# teensy_cfd.net
KiCad netlist of a schematic drawn in EAGLE
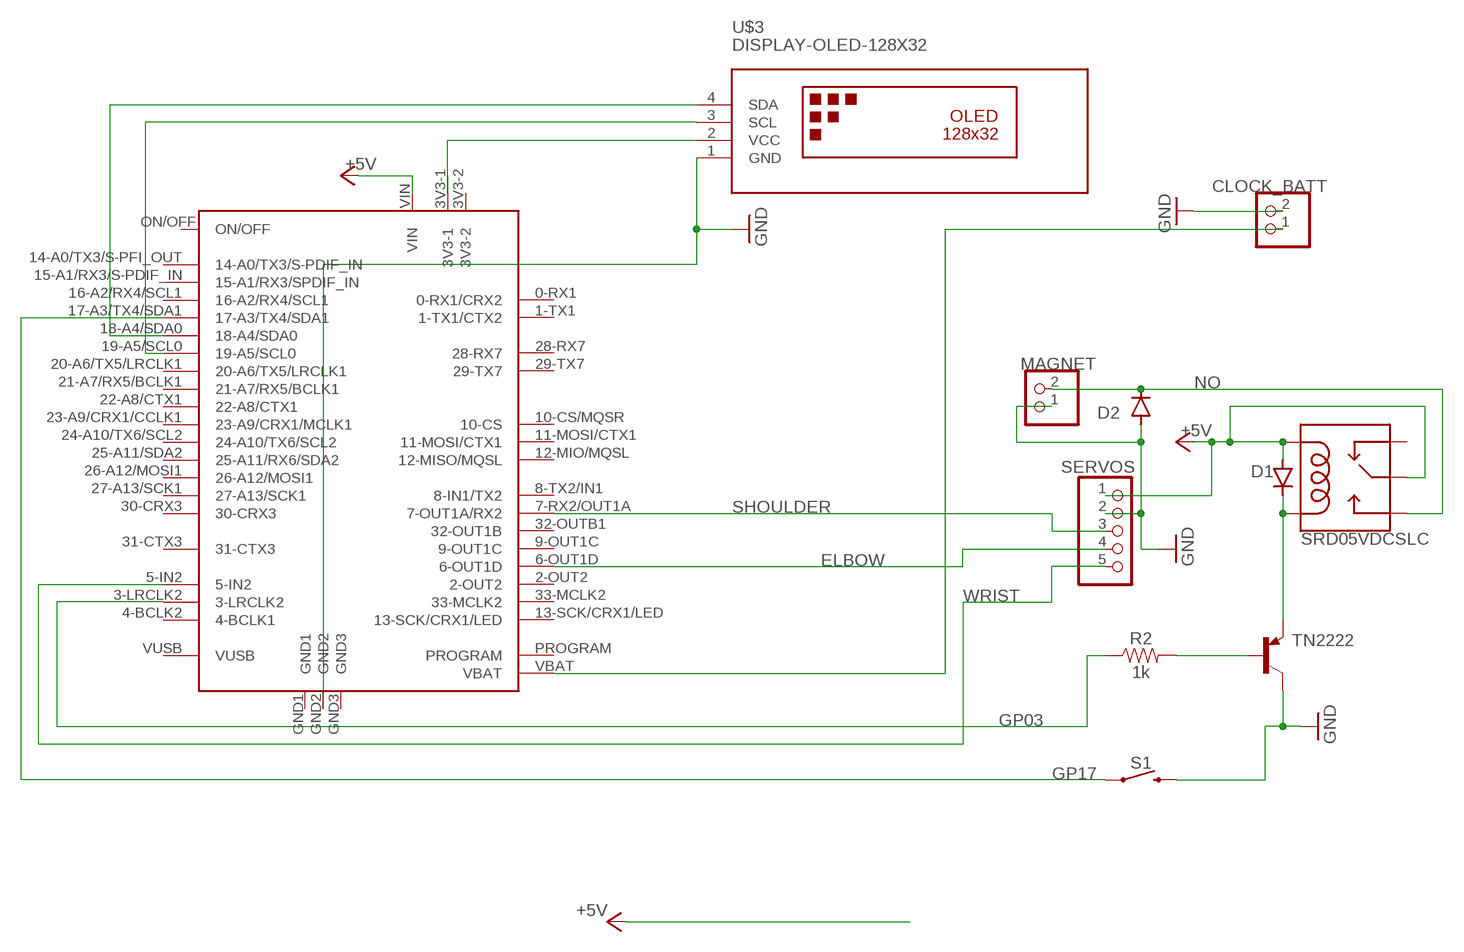
[diagram p0: schematic, sheet 1]

(export (version "E")
  (design (tool "Eeschema 10.0.6"))
  (components
    (comp (ref "CLOCK_BATT")
      (value "PINHD-1X2")
      (footprint "eagle-import:1X02")
      (libsource (lib "eagle-import") (part "PINHD-1X2"))
    )
    (comp (ref "D1")
      (value "1N4004")
      (footprint "eagle-import:DO41-10")
      (libsource (lib "eagle-import") (part "1N4004"))
    )
    (comp (ref "D2")
      (value "1N4004")
      (footprint "eagle-import:DO41-10")
      (libsource (lib "eagle-import") (part "1N4004"))
    )
    (comp (ref "MAGNET")
      (value "PINHD-1X2")
      (footprint "eagle-import:1X02")
      (libsource (lib "eagle-import") (part "PINHD-1X2"))
    )
    (comp (ref "R2")
      (value "1k")
      (footprint "eagle-import:AXIAL-0.3")
      (libsource (lib "eagle-import") (part "1KOHM-HORIZ-1/4W-1%"))
    )
    (comp (ref "S1")
      (value "MOMENTARY-SWITCH-SPST-PTH-6.0MM")
      (footprint "eagle-import:TACTILE_SWITCH_PTH_6.0MM")
      (libsource (lib "eagle-import") (part "MOMENTARY-SWITCH-SPST-PTH-6.0MM"))
    )
    (comp (ref "SERVOS")
      (value "PINHD-1X5")
      (footprint "eagle-import:1X05")
      (libsource (lib "eagle-import") (part "PINHD-1X5"))
    )
    (comp (ref "SRD05VDCSLC")
      (value "RELAYPTH")
      (footprint "eagle-import:SRD-05VDC-SL-C")
      (libsource (lib "eagle-import") (part "RELAYPTH"))
    )
    (comp (ref "TN2222")
      (value "TN2222")
      (footprint "eagle-import:TO92")
      (libsource (lib "eagle-import") (part "PNPTO92_"))
    )
    (comp (ref "U$1")
      (value "TEENSY40")
      (footprint "eagle-import:TEENSY40")
      (libsource (lib "eagle-import") (part "TEENSY40"))
    )
    (comp (ref "U$3")
      (value "DISPLAY-OLED-128X32")
      (footprint "eagle-import:DISPLAY-OLED-128X32")
      (libsource (lib "eagle-import") (part "DISPLAY-OLED-128X32"))
    )
  )
  (nets
    (net (code "1") (name "+5V") (class "Default")
      (node (ref "D1") (pin "A") (pinfunction "A_A") (pintype "passive"))
      (node (ref "SERVOS") (pin "1") (pinfunction "1_1") (pintype "passive"))
      (node (ref "SRD05VDCSLC") (pin "COIL1") (pinfunction "COIL1_COIL1") (pintype "bidirectional"))
      (node (ref "SRD05VDCSLC") (pin "SWCOMMON") (pinfunction "SWCOMMON_SWCOMMON") (pintype "bidirectional"))
      (node (ref "U$1") (pin "VIN") (pinfunction "VIN_VIN") (pintype "bidirectional"))
    )
    (net (code "2") (name "/ELBOW") (class "Default")
      (node (ref "SERVOS") (pin "4") (pinfunction "4_4") (pintype "passive"))
      (node (ref "U$1") (pin "6-OUT1D") (pinfunction "6-OUT1D_6-OUT1D") (pintype "bidirectional"))
    )
    (net (code "3") (name "/GP03") (class "Default")
      (node (ref "R2") (pin "P$1") (pinfunction "1_P$1") (pintype "passive"))
      (node (ref "U$1") (pin "3-LRCLK2") (pinfunction "3-LRCLK2_3-LRCLK2") (pintype "bidirectional"))
    )
    (net (code "4") (name "/GP17") (class "Default")
      (node (ref "S1") (pin "1") (pinfunction "1_1") (pintype "passive"))
      (node (ref "U$1") (pin "17-A3/TX4/SDA1") (pinfunction "17-A3/TX4/SDA1_17-A3/TX4/SDA1") (pintype "bidirectional"))
    )
    (net (code "5") (name "/NO") (class "Default")
      (node (ref "D2") (pin "C") (pinfunction "C_C") (pintype "passive"))
      (node (ref "MAGNET") (pin "2") (pinfunction "2_2") (pintype "passive"))
      (node (ref "SRD05VDCSLC") (pin "SWOPEN") (pinfunction "SWOPEN_SWOPEN") (pintype "bidirectional"))
    )
    (net (code "6") (name "/SHOULDER") (class "Default")
      (node (ref "SERVOS") (pin "3") (pinfunction "3_3") (pintype "passive"))
      (node (ref "U$1") (pin "7-RX2/OUT1A") (pinfunction "7-OUT1A/RX2_7-RX2/OUT1A") (pintype "bidirectional"))
    )
    (net (code "7") (name "/WRIST") (class "Default")
      (node (ref "SERVOS") (pin "5") (pinfunction "5_5") (pintype "passive"))
      (node (ref "U$1") (pin "5-IN2") (pinfunction "5-IN2_5-IN2") (pintype "bidirectional"))
    )
    (net (code "8") (name "GND") (class "Default")
      (node (ref "CLOCK_BATT") (pin "2") (pinfunction "2_2") (pintype "passive"))
      (node (ref "D2") (pin "A") (pinfunction "A_A") (pintype "passive"))
      (node (ref "MAGNET") (pin "1") (pinfunction "1_1") (pintype "passive"))
      (node (ref "S1") (pin "3") (pinfunction "2_3") (pintype "passive"))
      (node (ref "SERVOS") (pin "2") (pinfunction "2_2") (pintype "passive"))
      (node (ref "TN2222") (pin "1") (pinfunction "C_1") (pintype "passive"))
      (node (ref "U$1") (pin "GND2") (pinfunction "GND2_GND2") (pintype "bidirectional"))
      (node (ref "U$3") (pin "1") (pinfunction "GND_1") (pintype "power_in"))
    )
    (net (code "9") (name "Net-(CLOCK_BATT-Pad1)") (class "Default")
      (node (ref "CLOCK_BATT") (pin "1") (pinfunction "1_1") (pintype "passive"))
      (node (ref "U$1") (pin "VBAT") (pinfunction "VBAT_VBAT") (pintype "bidirectional"))
    )
    (net (code "10") (name "Net-(R2-2)") (class "Default")
      (node (ref "R2") (pin "P$2") (pinfunction "2_P$2") (pintype "passive"))
      (node (ref "TN2222") (pin "2") (pinfunction "B_2") (pintype "passive"))
    )
    (net (code "11") (name "Net-(TN2222-E)") (class "Default")
      (node (ref "D1") (pin "C") (pinfunction "C_C") (pintype "passive"))
      (node (ref "SRD05VDCSLC") (pin "COIL0") (pinfunction "COIL0_COIL0") (pintype "bidirectional"))
      (node (ref "TN2222") (pin "3") (pinfunction "E_3") (pintype "passive"))
    )
    (net (code "12") (name "Net-(U$3-SCL)") (class "Default")
      (node (ref "U$1") (pin "19-A5/SCL0") (pinfunction "19-A5/SCL0_19-A5/SCL0") (pintype "bidirectional"))
      (node (ref "U$3") (pin "3") (pinfunction "SCL_3") (pintype "bidirectional"))
    )
    (net (code "13") (name "Net-(U$3-SDA)") (class "Default")
      (node (ref "U$1") (pin "18-A4/SDA0") (pinfunction "18-A4/SDA0_18-A4/SDA0") (pintype "bidirectional"))
      (node (ref "U$3") (pin "4") (pinfunction "SDA_4") (pintype "bidirectional"))
    )
    (net (code "14") (name "Net-(U$3-VCC)") (class "Default")
      (node (ref "U$1") (pin "3V3-1") (pinfunction "3V3-1_3V3-1") (pintype "bidirectional"))
      (node (ref "U$3") (pin "2") (pinfunction "VCC_2") (pintype "power_in"))
    )
    (net (code "15") (name "unconnected-(SRD05VDCSLC-SWCLOSE-PadSWCLOSED)") (class "Default")
      (node (ref "SRD05VDCSLC") (pin "SWCLOSED") (pinfunction "SWCLOSE_SWCLOSED") (pintype "bidirectional"))
    )
    (net (code "16") (name "unconnected-(U$1-0-RX1{slash}CRX2-Pad0-RX1)") (class "Default")
      (node (ref "U$1") (pin "0-RX1") (pinfunction "0-RX1/CRX2_0-RX1") (pintype "bidirectional"))
    )
    (net (code "17") (name "unconnected-(U$1-1-TX1{slash}CTX2-Pad1-TX1)") (class "Default")
      (node (ref "U$1") (pin "1-TX1") (pinfunction "1-TX1/CTX2_1-TX1") (pintype "bidirectional"))
    )
    (net (code "18") (name "unconnected-(U$1-4-BCLK1-Pad4-BCLK2)") (class "Default")
      (node (ref "U$1") (pin "4-BCLK2") (pinfunction "4-BCLK1_4-BCLK2") (pintype "bidirectional"))
    )
    (net (code "19") (name "unconnected-(U$1-8-IN1{slash}TX2-Pad8-TX2{slash}IN1)") (class "Default")
      (node (ref "U$1") (pin "8-TX2/IN1") (pinfunction "8-IN1/TX2_8-TX2/IN1") (pintype "bidirectional"))
    )
    (net (code "20") (name "unconnected-(U$1-10-CS-Pad10-CS{slash}MQSR)") (class "Default")
      (node (ref "U$1") (pin "10-CS/MQSR") (pinfunction "10-CS_10-CS/MQSR") (pintype "bidirectional"))
    )
    (net (code "21") (name "unconnected-(U$1-12-MISO{slash}MQSL-Pad12-MIO{slash}MQSL)") (class "Default")
      (node (ref "U$1") (pin "12-MIO/MQSL") (pinfunction "12-MISO/MQSL_12-MIO/MQSL") (pintype "bidirectional"))
    )
    (net (code "22") (name "unconnected-(U$1-14-A0{slash}TX3{slash}S-PDIF_IN-Pad14-A0{slash}TX3{slash}S-PFI_OUT)") (class "Default")
      (node (ref "U$1") (pin "14-A0/TX3/S-PFI_OUT") (pinfunction "14-A0/TX3/S-PDIF_IN_14-A0/TX3/S-PFI_OUT") (pintype "bidirectional"))
    )
    (net (code "23") (name "unconnected-(U$1-15-A1{slash}RX3{slash}SPDIF_IN-Pad15-A1{slash}RX3{slash}S-PDIF_IN)") (class "Default")
      (node (ref "U$1") (pin "15-A1/RX3/S-PDIF_IN") (pinfunction "15-A1/RX3/SPDIF_IN_15-A1/RX3/S-PDIF_IN") (pintype "bidirectional"))
    )
    (net (code "24") (name "unconnected-(U$1-23-A9{slash}CRX1{slash}MCLK1-Pad23-A9{slash}CRX1{slash}CCLK1)") (class "Default")
      (node (ref "U$1") (pin "23-A9/CRX1/CCLK1") (pinfunction "23-A9/CRX1/MCLK1_23-A9/CRX1/CCLK1") (pintype "bidirectional"))
    )
    (net (code "25") (name "unconnected-(U$1-25-A11{slash}RX6{slash}SDA2-Pad25-A11{slash}SDA2)") (class "Default")
      (node (ref "U$1") (pin "25-A11/SDA2") (pinfunction "25-A11/RX6/SDA2_25-A11/SDA2") (pintype "bidirectional"))
    )
    (net (code "26") (name "unconnected-(U$1-32-OUT1B-Pad32-OUTB1)") (class "Default")
      (node (ref "U$1") (pin "32-OUTB1") (pinfunction "32-OUT1B_32-OUTB1") (pintype "bidirectional"))
    )
    (net (code "27") (name "unconnected-(U$1-Pad2-OUT2)") (class "Default")
      (node (ref "U$1") (pin "2-OUT2") (pinfunction "2-OUT2_2-OUT2") (pintype "bidirectional"))
    )
    (net (code "28") (name "unconnected-(U$1-Pad3V3-2)") (class "Default")
      (node (ref "U$1") (pin "3V3-2") (pinfunction "3V3-2_3V3-2") (pintype "bidirectional"))
    )
    (net (code "29") (name "unconnected-(U$1-Pad9-OUT1C)") (class "Default")
      (node (ref "U$1") (pin "9-OUT1C") (pinfunction "9-OUT1C_9-OUT1C") (pintype "bidirectional"))
    )
    (net (code "30") (name "unconnected-(U$1-Pad11-MOSI{slash}CTX1)") (class "Default")
      (node (ref "U$1") (pin "11-MOSI/CTX1") (pinfunction "11-MOSI/CTX1_11-MOSI/CTX1") (pintype "bidirectional"))
    )
    (net (code "31") (name "unconnected-(U$1-Pad13-SCK{slash}CRX1{slash}LED)") (class "Default")
      (node (ref "U$1") (pin "13-SCK/CRX1/LED") (pinfunction "13-SCK/CRX1/LED_13-SCK/CRX1/LED") (pintype "bidirectional"))
    )
    (net (code "32") (name "unconnected-(U$1-Pad16-A2{slash}RX4{slash}SCL1)") (class "Default")
      (node (ref "U$1") (pin "16-A2/RX4/SCL1") (pinfunction "16-A2/RX4/SCL1_16-A2/RX4/SCL1") (pintype "bidirectional"))
    )
    (net (code "33") (name "unconnected-(U$1-Pad20-A6{slash}TX5{slash}LRCLK1)") (class "Default")
      (node (ref "U$1") (pin "20-A6/TX5/LRCLK1") (pinfunction "20-A6/TX5/LRCLK1_20-A6/TX5/LRCLK1") (pintype "bidirectional"))
    )
    (net (code "34") (name "unconnected-(U$1-Pad21-A7{slash}RX5{slash}BCLK1)") (class "Default")
      (node (ref "U$1") (pin "21-A7/RX5/BCLK1") (pinfunction "21-A7/RX5/BCLK1_21-A7/RX5/BCLK1") (pintype "bidirectional"))
    )
    (net (code "35") (name "unconnected-(U$1-Pad22-A8{slash}CTX1)") (class "Default")
      (node (ref "U$1") (pin "22-A8/CTX1") (pinfunction "22-A8/CTX1_22-A8/CTX1") (pintype "bidirectional"))
    )
    (net (code "36") (name "unconnected-(U$1-Pad24-A10{slash}TX6{slash}SCL2)") (class "Default")
      (node (ref "U$1") (pin "24-A10/TX6/SCL2") (pinfunction "24-A10/TX6/SCL2_24-A10/TX6/SCL2") (pintype "bidirectional"))
    )
    (net (code "37") (name "unconnected-(U$1-Pad26-A12{slash}MOSI1)") (class "Default")
      (node (ref "U$1") (pin "26-A12/MOSI1") (pinfunction "26-A12/MOSI1_26-A12/MOSI1") (pintype "bidirectional"))
    )
    (net (code "38") (name "unconnected-(U$1-Pad27-A13{slash}SCK1)") (class "Default")
      (node (ref "U$1") (pin "27-A13/SCK1") (pinfunction "27-A13/SCK1_27-A13/SCK1") (pintype "bidirectional"))
    )
    (net (code "39") (name "unconnected-(U$1-Pad28-RX7)") (class "Default")
      (node (ref "U$1") (pin "28-RX7") (pinfunction "28-RX7_28-RX7") (pintype "bidirectional"))
    )
    (net (code "40") (name "unconnected-(U$1-Pad29-TX7)") (class "Default")
      (node (ref "U$1") (pin "29-TX7") (pinfunction "29-TX7_29-TX7") (pintype "bidirectional"))
    )
    (net (code "41") (name "unconnected-(U$1-Pad30-CRX3)") (class "Default")
      (node (ref "U$1") (pin "30-CRX3") (pinfunction "30-CRX3_30-CRX3") (pintype "bidirectional"))
    )
    (net (code "42") (name "unconnected-(U$1-Pad31-CTX3)") (class "Default")
      (node (ref "U$1") (pin "31-CTX3") (pinfunction "31-CTX3_31-CTX3") (pintype "bidirectional"))
    )
    (net (code "43") (name "unconnected-(U$1-Pad33-MCLK2)") (class "Default")
      (node (ref "U$1") (pin "33-MCLK2") (pinfunction "33-MCLK2_33-MCLK2") (pintype "bidirectional"))
    )
    (net (code "44") (name "unconnected-(U$1-PadGND1)") (class "Default")
      (node (ref "U$1") (pin "GND1") (pinfunction "GND1_GND1") (pintype "bidirectional"))
    )
    (net (code "45") (name "unconnected-(U$1-PadGND3)") (class "Default")
      (node (ref "U$1") (pin "GND3") (pinfunction "GND3_GND3") (pintype "bidirectional"))
    )
    (net (code "46") (name "unconnected-(U$1-PadON{slash}OFF)") (class "Default")
      (node (ref "U$1") (pin "ON/OFF") (pinfunction "ON/OFF_ON/OFF") (pintype "bidirectional"))
    )
    (net (code "47") (name "unconnected-(U$1-PadPROGRAM)") (class "Default")
      (node (ref "U$1") (pin "PROGRAM") (pinfunction "PROGRAM_PROGRAM") (pintype "bidirectional"))
    )
    (net (code "48") (name "unconnected-(U$1-PadVUSB)") (class "Default")
      (node (ref "U$1") (pin "VUSB") (pinfunction "VUSB_VUSB") (pintype "bidirectional"))
    )
  )
)
